# Power.net
KiCad netlist of a schematic drawn in Altium Designer
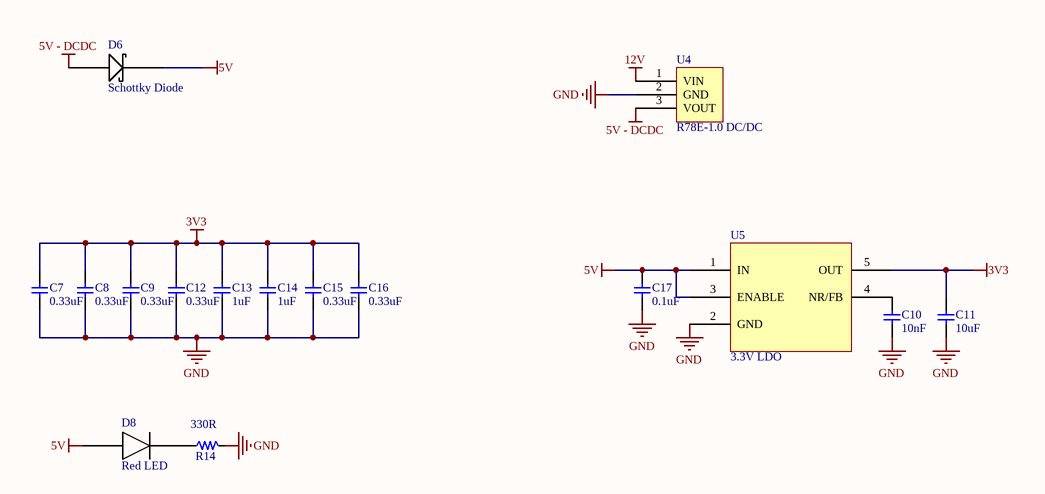
[diagram p0: Power.SchDoc]

(export (version "E")
  (design (tool "Eeschema 10.0.6"))
  (components
    (comp (ref "C7")
      (value "0.33uF")
      (footprint "PCB_GENERIC_SMD_0603")
      (description "CAP CER 0603 1uF 16V X5R 20%")
      (fields (field (name "TOLERANCE") "20%") (field (name "VOLTAGE") "16V"))
      (libsource (lib "CAP-0603") (part "C060-0001U-00"))
    )
    (comp (ref "C8")
      (value "0.33uF")
      (footprint "PCB_GENERIC_SMD_0603")
      (description "CAP CER 0603 1uF 16V X5R 20%")
      (fields (field (name "TOLERANCE") "20%") (field (name "VOLTAGE") "16V"))
      (libsource (lib "CAP-0603") (part "C060-0001U-00"))
    )
    (comp (ref "C9")
      (value "0.33uF")
      (footprint "PCB_GENERIC_SMD_0603")
      (description "CAP CER 0603 1uF 16V X5R 20%")
      (fields (field (name "TOLERANCE") "20%") (field (name "VOLTAGE") "16V"))
      (libsource (lib "CAP-0603") (part "C060-0001U-00"))
    )
    (comp (ref "C10")
      (value "10nF")
      (footprint "PCB_GENERIC_SMD_0603")
      (description "CAP CER 0603 1uF 16V X5R 20%")
      (fields (field (name "TOLERANCE") "20%") (field (name "VOLTAGE") "16V"))
      (libsource (lib "CAP-0603") (part "C060-0001U-00"))
    )
    (comp (ref "C11")
      (value "10uF")
      (footprint "PCB_GENERIC_SMD_0603")
      (description "CAP CER 0603 1uF 16V X5R 20%")
      (fields (field (name "TOLERANCE") "20%") (field (name "VOLTAGE") "16V"))
      (libsource (lib "CAP-0603") (part "C060-0001U-00"))
    )
    (comp (ref "C12")
      (value "0.33uF")
      (footprint "PCB_GENERIC_SMD_0603")
      (description "CAP CER 0603 1uF 16V X5R 20%")
      (fields (field (name "TOLERANCE") "20%") (field (name "VOLTAGE") "16V"))
      (libsource (lib "CAP-0603") (part "C060-0001U-00"))
    )
    (comp (ref "C13")
      (value "1uF")
      (footprint "PCB_GENERIC_SMD_0603")
      (description "CAP CER 0603 1uF 16V X5R 20%")
      (fields (field (name "TOLERANCE") "20%") (field (name "VOLTAGE") "16V"))
      (libsource (lib "CAP-0603") (part "C060-0001U-00"))
    )
    (comp (ref "C14")
      (value "1uF")
      (footprint "PCB_GENERIC_SMD_0603")
      (description "CAP CER 0603 1uF 16V X5R 20%")
      (fields (field (name "TOLERANCE") "20%") (field (name "VOLTAGE") "16V"))
      (libsource (lib "CAP-0603") (part "C060-0001U-00"))
    )
    (comp (ref "C15")
      (value "0.33uF")
      (footprint "PCB_GENERIC_SMD_0603")
      (description "CAP CER 0603 1uF 16V X5R 20%")
      (fields (field (name "TOLERANCE") "20%") (field (name "VOLTAGE") "16V"))
      (libsource (lib "CAP-0603") (part "C060-0001U-00"))
    )
    (comp (ref "C16")
      (value "0.33uF")
      (footprint "PCB_GENERIC_SMD_0603")
      (description "CAP CER 0603 1uF 16V X5R 20%")
      (fields (field (name "TOLERANCE") "20%") (field (name "VOLTAGE") "16V"))
      (libsource (lib "CAP-0603") (part "C060-0001U-00"))
    )
    (comp (ref "C17")
      (value "0.1uF")
      (footprint "PCB_GENERIC_SMD_0603")
      (description "CAP CER 0603 1uF 16V X5R 20%")
      (fields (field (name "TOLERANCE") "20%") (field (name "VOLTAGE") "16V"))
      (libsource (lib "CAP-0603") (part "C060-0001U-00"))
    )
    (comp (ref "D6")
      (value "Schottky Diode")
      (footprint "ON Semi Schottky Diode - MBRM110LT1G")
      (libsource (lib "ON Semi Schottky Diode - MBRM110LT1G") (part "ON Semi Schottky Diode - MBRM110LT1G"))
    )
    (comp (ref "D8")
      (value "Red LED")
      (footprint "SMD_0603_LED")
      (libsource (lib "SMD_0603_LED") (part "SMD_0603_LED"))
    )
    (comp (ref "R14")
      (value "SCH_GENERIC_RESISTOR_0603")
      (footprint "PCB_GENERIC_SMD_0603")
      (description "Generic SMD resistor 0603")
      (fields (field (name "RESISTANCE") "330R"))
      (libsource (lib "SCH_GENERIC_RESISTOR_0603") (part "SCH_GENERIC_RESISTOR_0603"))
    )
    (comp (ref "U4")
      (value "R78E-1.0 DC/DC")
      (footprint "R78-1.0")
      (libsource (lib "R78E-1.0_DCDC_SCH") (part "R78E-1.0"))
    )
    (comp (ref "U5")
      (value "3.3V LDO")
      (footprint "SOT95P280X145-5N")
      (description "Linear Voltage Regulator IC Positive Fixed 1 Output 3.3V 400mA SOT-23-5")
      (libsource (lib "3V3LDO_TPS73633DBVR_SOT23-5") (part "3V3LDO_TPS73633DBVR_SOT23-5"))
    )
  )
  (nets
    (net (code "1") (name "3V3") (class "Default")
      (node (ref "C11") (pin "2") (pinfunction "2_2") (pintype "passive"))
      (node (ref "C12") (pin "2") (pinfunction "2_2") (pintype "passive"))
      (node (ref "C13") (pin "1") (pinfunction "1_1") (pintype "passive"))
      (node (ref "C14") (pin "1") (pinfunction "1_1") (pintype "passive"))
      (node (ref "C15") (pin "2") (pinfunction "2_2") (pintype "passive"))
      (node (ref "C16") (pin "2") (pinfunction "2_2") (pintype "passive"))
      (node (ref "C7") (pin "2") (pinfunction "2_2") (pintype "passive"))
      (node (ref "C8") (pin "2") (pinfunction "2_2") (pintype "passive"))
      (node (ref "C9") (pin "2") (pinfunction "2_2") (pintype "passive"))
      (node (ref "U5") (pin "5") (pinfunction "OUT_5") (pintype "power_in"))
    )
    (net (code "2") (name "5V") (class "Default")
      (node (ref "C17") (pin "2") (pinfunction "2_2") (pintype "passive"))
      (node (ref "D6") (pin "1") (pinfunction "1_1") (pintype "passive"))
      (node (ref "D8") (pin "1") (pinfunction "1_1") (pintype "passive"))
      (node (ref "U5") (pin "1") (pinfunction "IN_1") (pintype "power_in"))
      (node (ref "U5") (pin "3") (pinfunction "ENABLE_3") (pintype "power_in"))
    )
    (net (code "3") (name "5V - DCDC") (class "Default")
      (node (ref "D6") (pin "2") (pinfunction "2_2") (pintype "passive"))
      (node (ref "U4") (pin "3") (pinfunction "VOUT_3") (pintype "passive"))
    )
    (net (code "4") (name "12V") (class "Default")
      (node (ref "U4") (pin "1") (pinfunction "VIN_1") (pintype "passive"))
    )
    (net (code "5") (name "GND") (class "Default")
      (node (ref "C10") (pin "1") (pinfunction "1_1") (pintype "passive"))
      (node (ref "C11") (pin "1") (pinfunction "1_1") (pintype "passive"))
      (node (ref "C12") (pin "1") (pinfunction "1_1") (pintype "passive"))
      (node (ref "C13") (pin "2") (pinfunction "2_2") (pintype "passive"))
      (node (ref "C14") (pin "2") (pinfunction "2_2") (pintype "passive"))
      (node (ref "C15") (pin "1") (pinfunction "1_1") (pintype "passive"))
      (node (ref "C16") (pin "1") (pinfunction "1_1") (pintype "passive"))
      (node (ref "C17") (pin "1") (pinfunction "1_1") (pintype "passive"))
      (node (ref "C7") (pin "1") (pinfunction "1_1") (pintype "passive"))
      (node (ref "C8") (pin "1") (pinfunction "1_1") (pintype "passive"))
      (node (ref "C9") (pin "1") (pinfunction "1_1") (pintype "passive"))
      (node (ref "R14") (pin "2") (pinfunction "2_2") (pintype "passive"))
      (node (ref "U4") (pin "2") (pinfunction "GND_2") (pintype "passive"))
      (node (ref "U5") (pin "2") (pinfunction "GND_2") (pintype "power_in"))
    )
    (net (code "6") (name "Net-(D8-Pad2)") (class "Default")
      (node (ref "D8") (pin "2") (pinfunction "2_2") (pintype "passive"))
      (node (ref "R14") (pin "1") (pinfunction "1_1") (pintype "passive"))
    )
    (net (code "7") (name "Net-(U5-NR{slash}FB)") (class "Default")
      (node (ref "C10") (pin "2") (pinfunction "2_2") (pintype "passive"))
      (node (ref "U5") (pin "4") (pinfunction "NR/FB_4") (pintype "power_in"))
    )
  )
)
